# I2C-SPI.net
KiCad netlist of a schematic drawn in Altium Designer
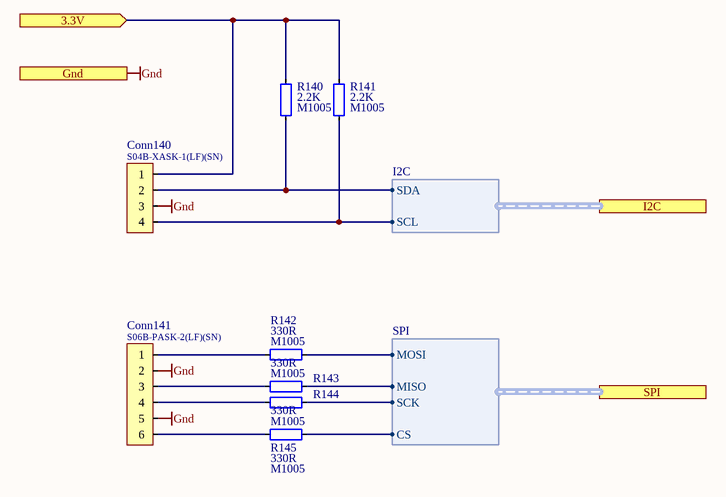
[diagram p0: I2C-SPI.SchDoc]

(export (version "E")
  (design (tool "Eeschema 10.0.6"))
  (components
    (comp (ref "Conn140")
      (value "Connector - 4P")
      (footprint "Connector, S04B-XASK-1")
      (description "Conn, JST, 4P, TH, XA, Side Entry")
      (fields
        (field (name "MANUFACTURER") "JST")
        (field (name "MANUFACTURER PART NUMBER") "S04B-XASK-1(LF)(SN)")
      )
      (libsource (lib "Connector - JST") (part "Connector - 4P"))
    )
    (comp (ref "Conn141")
      (value "Connector - 6P")
      (footprint "Connector, S06B-PASK-2")
      (description "Conn, JST, 6P, TH, PA, Side Entry")
      (fields
        (field (name "MANUFACTURER") "JST")
        (field (name "MANUFACTURER PART NUMBER") "S06B-PASK-2(LF)(SN)")
      )
      (libsource (lib "Connector - JST") (part "Connector - 6P"))
    )
    (comp (ref "R140")
      (value "2.2K")
      (footprint "Resistor_Smd_M1005_I0402")
      (description "Res, 2.2K, 1%, M1005")
      (fields
        (field (name "TOLERANCE") "1%")
        (field (name "MANUFACTURER") "Yageo")
        (field (name "PACKAGE") "M1005")
      )
      (libsource (lib "Resistor") (part "Resistor"))
    )
    (comp (ref "R141")
      (value "2.2K")
      (footprint "Resistor_Smd_M1005_I0402")
      (description "Res, 2.2K, 1%, M1005")
      (fields
        (field (name "TOLERANCE") "1%")
        (field (name "MANUFACTURER") "Yageo")
        (field (name "PACKAGE") "M1005")
      )
      (libsource (lib "Resistor") (part "Resistor"))
    )
    (comp (ref "R142")
      (value "330R")
      (footprint "Resistor_Smd_M1005_I0402")
      (description "Res, 330R, 1%, M1005")
      (fields
        (field (name "TOLERANCE") "1%")
        (field (name "MANUFACTURER") "Yageo")
        (field (name "PACKAGE") "M1005")
      )
      (libsource (lib "Resistor") (part "Resistor"))
    )
    (comp (ref "R143")
      (value "330R")
      (footprint "Resistor_Smd_M1005_I0402")
      (description "Res, 330R, 1%, M1005")
      (fields
        (field (name "TOLERANCE") "1%")
        (field (name "MANUFACTURER") "Yageo")
        (field (name "PACKAGE") "M1005")
      )
      (libsource (lib "Resistor") (part "Resistor"))
    )
    (comp (ref "R144")
      (value "330R")
      (footprint "Resistor_Smd_M1005_I0402")
      (description "Res, 330R, 1%, M1005")
      (fields
        (field (name "TOLERANCE") "1%")
        (field (name "MANUFACTURER") "Yageo")
        (field (name "PACKAGE") "M1005")
      )
      (libsource (lib "Resistor") (part "Resistor"))
    )
    (comp (ref "R145")
      (value "330R")
      (footprint "Resistor_Smd_M1005_I0402")
      (description "Res, 330R, 1%, M1005")
      (fields
        (field (name "TOLERANCE") "1%")
        (field (name "MANUFACTURER") "Yageo")
        (field (name "PACKAGE") "M1005")
      )
      (libsource (lib "Resistor") (part "Resistor"))
    )
  )
  (nets
    (net (code "3") (name "/3.3V") (class "Default")
      (node (ref "Conn140") (pin "1") (pinfunction "1_1") (pintype "passive"))
      (node (ref "R140") (pin "1") (pinfunction "1_1") (pintype "passive"))
      (node (ref "R141") (pin "1") (pinfunction "1_1") (pintype "passive"))
    )
    (net (code "4") (name "/CS") (class "Default")
      (node (ref "R145") (pin "2") (pinfunction "2_2") (pintype "passive"))
    )
    (net (code "5") (name "/MISO") (class "Default")
      (node (ref "R143") (pin "2") (pinfunction "2_2") (pintype "passive"))
    )
    (net (code "6") (name "/MOSI") (class "Default")
      (node (ref "R142") (pin "2") (pinfunction "2_2") (pintype "passive"))
    )
    (net (code "7") (name "/SCK") (class "Default")
      (node (ref "R144") (pin "2") (pinfunction "2_2") (pintype "passive"))
    )
    (net (code "8") (name "/SCL") (class "Default")
      (node (ref "Conn140") (pin "4") (pinfunction "4_4") (pintype "passive"))
      (node (ref "R141") (pin "2") (pinfunction "2_2") (pintype "passive"))
    )
    (net (code "9") (name "/SDA") (class "Default")
      (node (ref "Conn140") (pin "2") (pinfunction "2_2") (pintype "passive"))
      (node (ref "R140") (pin "2") (pinfunction "2_2") (pintype "passive"))
    )
    (net (code "12") (name "Gnd") (class "Default")
      (node (ref "Conn140") (pin "3") (pinfunction "3_3") (pintype "passive"))
      (node (ref "Conn141") (pin "2") (pinfunction "2_2") (pintype "passive"))
      (node (ref "Conn141") (pin "5") (pinfunction "5_5") (pintype "passive"))
    )
    (net (code "13") (name "Net-(Conn141-Pad1)") (class "Default")
      (node (ref "Conn141") (pin "1") (pinfunction "1_1") (pintype "passive"))
      (node (ref "R142") (pin "1") (pinfunction "1_1") (pintype "passive"))
    )
    (net (code "14") (name "Net-(Conn141-Pad3)") (class "Default")
      (node (ref "Conn141") (pin "3") (pinfunction "3_3") (pintype "passive"))
      (node (ref "R143") (pin "1") (pinfunction "1_1") (pintype "passive"))
    )
    (net (code "15") (name "Net-(Conn141-Pad4)") (class "Default")
      (node (ref "Conn141") (pin "4") (pinfunction "4_4") (pintype "passive"))
      (node (ref "R144") (pin "1") (pinfunction "1_1") (pintype "passive"))
    )
    (net (code "16") (name "Net-(Conn141-Pad6)") (class "Default")
      (node (ref "Conn141") (pin "6") (pinfunction "6_6") (pintype "passive"))
      (node (ref "R145") (pin "1") (pinfunction "1_1") (pintype "passive"))
    )
  )
)
